# Door_Lock_DE_12.net
KiCad netlist of a schematic drawn in EAGLE
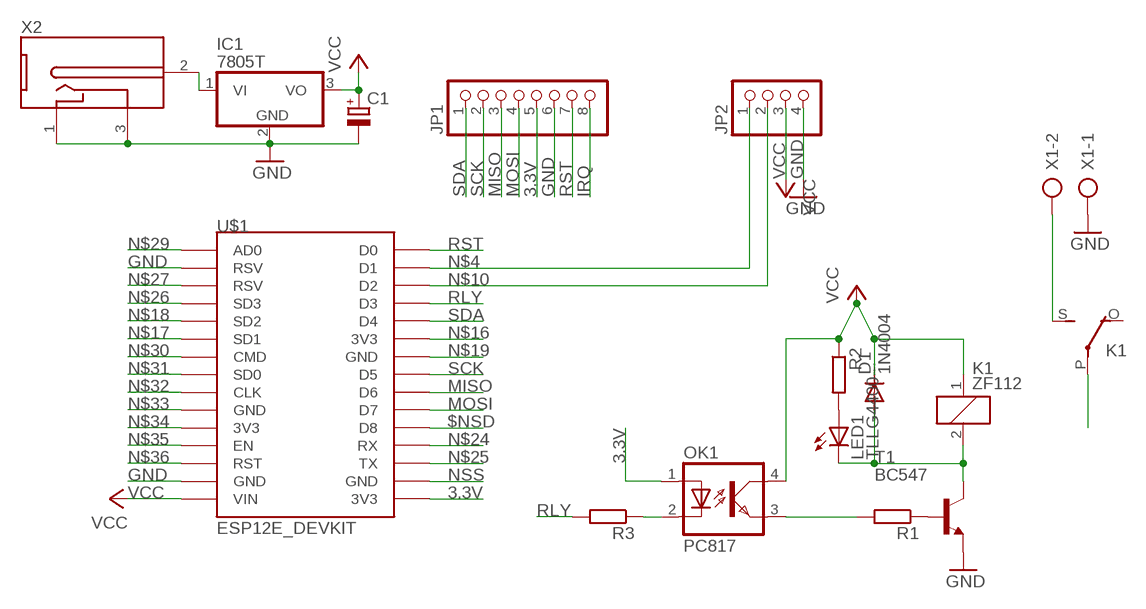
[diagram p0: schematic, sheet 1]

(export (version "E")
  (design (tool "Eeschema 10.0.6"))
  (components
    (comp (ref "C1")
      (value "CPOL-EUE3.5-8")
      (footprint "eagle-import:E3,5-8")
      (libsource (lib "eagle-import") (part "CPOL-EUE3.5-8"))
    )
    (comp (ref "D1")
      (value "1N4004")
      (footprint "eagle-import:DO41-10")
      (libsource (lib "eagle-import") (part "1N4004"))
    )
    (comp (ref "IC1")
      (value "7805T")
      (footprint "eagle-import:TO220H")
      (libsource (lib "eagle-import") (part "78T05"))
    )
    (comp (ref "JP1")
      (value "PINHD-1X8")
      (footprint "eagle-import:1X08")
      (libsource (lib "eagle-import") (part "PINHD-1X8"))
    )
    (comp (ref "JP2")
      (value "PINHD-1X4")
      (footprint "eagle-import:1X04")
      (libsource (lib "eagle-import") (part "PINHD-1X4"))
    )
    (comp (ref "K1")
      (value "ZF112")
      (footprint "eagle-import:ZF112")
      (libsource (lib "eagle-import") (part "ZF112"))
    )
    (comp (ref "LED1")
      (value "TLLG4400")
      (footprint "eagle-import:LED3MM")
      (fields (field (name "MF") "VISHAY SEMICONDUCTOR"))
      (libsource (lib "eagle-import") (part "TLLG4400"))
    )
    (comp (ref "OK1")
      (value "PC817")
      (footprint "eagle-import:DIL04")
      (fields (field (name "MPN") "PC817X4J000F"))
      (libsource (lib "eagle-import") (part "PC817"))
    )
    (comp (ref "R1")
      (value "R-EU_0204/7")
      (footprint "eagle-import:0204_7")
      (libsource (lib "eagle-import") (part "R-EU_0204/7"))
    )
    (comp (ref "R2")
      (value "R-EU_0204/7")
      (footprint "eagle-import:0204_7")
      (libsource (lib "eagle-import") (part "R-EU_0204/7"))
    )
    (comp (ref "R3")
      (value "R-EU_0204/7")
      (footprint "eagle-import:0204_7")
      (libsource (lib "eagle-import") (part "R-EU_0204/7"))
    )
    (comp (ref "T1")
      (value "BC547")
      (footprint "eagle-import:TO92")
      (libsource (lib "eagle-import") (part "BC547"))
    )
    (comp (ref "U$1")
      (value "ESP12E_DEVKIT")
      (footprint "eagle-import:ESP12E_DEVKIT")
      (libsource (lib "eagle-import") (part "ESP12E_DEVKIT"))
    )
    (comp (ref "X1")
      (value "AK300/2")
      (footprint "eagle-import:AK300_2")
      (libsource (lib "eagle-import") (part "AK300/2"))
    )
    (comp (ref "X2")
      (value "DC-2.1MM-5MM")
      (footprint "eagle-import:DC-21MM")
      (libsource (lib "eagle-import") (part "DC-5MM-2.1MM"))
    )
  )
  (nets
    (net (code "1") (name "/$NSD") (class "Default")
      (node (ref "U$1") (pin "D8") (pinfunction "D8_D8") (pintype "bidirectional"))
    )
    (net (code "2") (name "/3.3V") (class "Default")
      (node (ref "JP1") (pin "5") (pinfunction "5_5") (pintype "passive"))
      (node (ref "OK1") (pin "1") (pinfunction "A_1") (pintype "passive"))
      (node (ref "U$1") (pin "3V3@2") (pinfunction "3V3_3V3@2") (pintype "bidirectional"))
    )
    (net (code "3") (name "/IRQ") (class "Default")
      (node (ref "JP1") (pin "8") (pinfunction "8_8") (pintype "passive"))
    )
    (net (code "4") (name "/MISO") (class "Default")
      (node (ref "JP1") (pin "3") (pinfunction "3_3") (pintype "passive"))
      (node (ref "U$1") (pin "D6") (pinfunction "D6_D6") (pintype "bidirectional"))
    )
    (net (code "5") (name "/MOSI") (class "Default")
      (node (ref "JP1") (pin "4") (pinfunction "4_4") (pintype "passive"))
      (node (ref "U$1") (pin "D7") (pinfunction "D7_D7") (pintype "bidirectional"))
    )
    (net (code "6") (name "/N$4") (class "Default")
      (node (ref "JP2") (pin "1") (pinfunction "1_1") (pintype "passive"))
      (node (ref "U$1") (pin "D1") (pinfunction "D1_D1") (pintype "bidirectional"))
    )
    (net (code "7") (name "/N$10") (class "Default")
      (node (ref "JP2") (pin "2") (pinfunction "2_2") (pintype "passive"))
      (node (ref "U$1") (pin "D2") (pinfunction "D2_D2") (pintype "bidirectional"))
    )
    (net (code "8") (name "/N$16") (class "Default")
      (node (ref "U$1") (pin "3V3@1") (pinfunction "3V3_3V3@1") (pintype "bidirectional"))
    )
    (net (code "9") (name "/N$17") (class "Default")
      (node (ref "U$1") (pin "SD1") (pinfunction "SD1_SD1") (pintype "bidirectional"))
    )
    (net (code "10") (name "/N$18") (class "Default")
      (node (ref "U$1") (pin "SD2") (pinfunction "SD2_SD2") (pintype "bidirectional"))
    )
    (net (code "11") (name "/N$19") (class "Default")
      (node (ref "U$1") (pin "GND@2") (pinfunction "GND_GND@2") (pintype "bidirectional"))
    )
    (net (code "12") (name "/N$24") (class "Default")
      (node (ref "U$1") (pin "RX") (pinfunction "RX_RX") (pintype "bidirectional"))
    )
    (net (code "13") (name "/N$25") (class "Default")
      (node (ref "U$1") (pin "TX") (pinfunction "TX_TX") (pintype "bidirectional"))
    )
    (net (code "14") (name "/N$26") (class "Default")
      (node (ref "U$1") (pin "SD3") (pinfunction "SD3_SD3") (pintype "bidirectional"))
    )
    (net (code "15") (name "/N$27") (class "Default")
      (node (ref "U$1") (pin "RSV@1") (pinfunction "RSV_RSV@1") (pintype "bidirectional"))
    )
    (net (code "16") (name "/N$29") (class "Default")
      (node (ref "U$1") (pin "AD0") (pinfunction "AD0_AD0") (pintype "bidirectional"))
    )
    (net (code "17") (name "/N$30") (class "Default")
      (node (ref "U$1") (pin "CMD") (pinfunction "CMD_CMD") (pintype "bidirectional"))
    )
    (net (code "18") (name "/N$31") (class "Default")
      (node (ref "U$1") (pin "SD0") (pinfunction "SD0_SD0") (pintype "bidirectional"))
    )
    (net (code "19") (name "/N$32") (class "Default")
      (node (ref "U$1") (pin "CLK") (pinfunction "CLK_CLK") (pintype "bidirectional"))
    )
    (net (code "20") (name "/N$33") (class "Default")
      (node (ref "U$1") (pin "GND@0") (pinfunction "GND_GND@0") (pintype "bidirectional"))
    )
    (net (code "21") (name "/N$34") (class "Default")
      (node (ref "U$1") (pin "3V3@0") (pinfunction "3V3_3V3@0") (pintype "bidirectional"))
    )
    (net (code "22") (name "/N$35") (class "Default")
      (node (ref "U$1") (pin "EN") (pinfunction "EN_EN") (pintype "bidirectional"))
    )
    (net (code "23") (name "/N$36") (class "Default")
      (node (ref "U$1") (pin "RST") (pinfunction "RST_RST") (pintype "bidirectional"))
    )
    (net (code "24") (name "/NSS") (class "Default")
      (node (ref "U$1") (pin "GND@3") (pinfunction "GND_GND@3") (pintype "bidirectional"))
    )
    (net (code "25") (name "/RLY") (class "Default")
      (node (ref "R3") (pin "2") (pinfunction "2_2") (pintype "passive"))
      (node (ref "U$1") (pin "D3") (pinfunction "D3_D3") (pintype "bidirectional"))
    )
    (net (code "26") (name "/RST") (class "Default")
      (node (ref "JP1") (pin "7") (pinfunction "7_7") (pintype "passive"))
      (node (ref "U$1") (pin "D0") (pinfunction "D0_D0") (pintype "bidirectional"))
    )
    (net (code "27") (name "/SCK") (class "Default")
      (node (ref "JP1") (pin "2") (pinfunction "2_2") (pintype "passive"))
      (node (ref "U$1") (pin "D5") (pinfunction "D5_D5") (pintype "bidirectional"))
    )
    (net (code "28") (name "/SDA") (class "Default")
      (node (ref "JP1") (pin "1") (pinfunction "1_1") (pintype "passive"))
      (node (ref "U$1") (pin "D4") (pinfunction "D4_D4") (pintype "bidirectional"))
    )
    (net (code "29") (name "GND") (class "Default")
      (node (ref "C1") (pin "-") (pinfunction "-_-") (pintype "passive"))
      (node (ref "IC1") (pin "2") (pinfunction "GND_2") (pintype "passive"))
      (node (ref "JP1") (pin "6") (pinfunction "6_6") (pintype "passive"))
      (node (ref "JP2") (pin "4") (pinfunction "4_4") (pintype "passive"))
      (node (ref "T1") (pin "1") (pinfunction "E_1") (pintype "passive"))
      (node (ref "U$1") (pin "GND@1") (pinfunction "GND_GND@1") (pintype "bidirectional"))
      (node (ref "U$1") (pin "RSV@0") (pinfunction "RSV_RSV@0") (pintype "bidirectional"))
      (node (ref "X1") (pin "1") (pinfunction "KL_1") (pintype "passive"))
      (node (ref "X2") (pin "1") (pinfunction "1_1") (pintype "power_in"))
      (node (ref "X2") (pin "3") (pinfunction "2_3") (pintype "power_in"))
    )
    (net (code "30") (name "Net-(IC1-VI)") (class "Default")
      (node (ref "IC1") (pin "1") (pinfunction "VI_1") (pintype "input"))
      (node (ref "X2") (pin "2") (pinfunction "3_2") (pintype "power_in"))
    )
    (net (code "31") (name "Net-(LED1-C)") (class "Default")
      (node (ref "D1") (pin "A") (pinfunction "A_A") (pintype "passive"))
      (node (ref "K1") (pin "2") (pinfunction "2_2") (pintype "passive"))
      (node (ref "LED1") (pin "K") (pinfunction "C_K") (pintype "passive"))
      (node (ref "T1") (pin "3") (pinfunction "C_3") (pintype "passive"))
    )
    (net (code "32") (name "Net-(LED1-PadA)") (class "Default")
      (node (ref "LED1") (pin "A") (pinfunction "A_A") (pintype "passive"))
      (node (ref "R2") (pin "2") (pinfunction "2_2") (pintype "passive"))
    )
    (net (code "33") (name "Net-(OK1-C)") (class "Default")
      (node (ref "OK1") (pin "2") (pinfunction "C_2") (pintype "passive"))
      (node (ref "R3") (pin "1") (pinfunction "1_1") (pintype "passive"))
    )
    (net (code "34") (name "Net-(OK1-EMIT)") (class "Default")
      (node (ref "OK1") (pin "3") (pinfunction "EMIT_3") (pintype "passive"))
      (node (ref "R1") (pin "2") (pinfunction "2_2") (pintype "passive"))
    )
    (net (code "35") (name "Net-(T1-B)") (class "Default")
      (node (ref "R1") (pin "1") (pinfunction "1_1") (pintype "passive"))
      (node (ref "T1") (pin "2") (pinfunction "B_2") (pintype "passive"))
    )
    (net (code "36") (name "Net-(X1B-KL)") (class "Default")
      (node (ref "K1") (pin "S") (pinfunction "S_S") (pintype "passive"))
      (node (ref "X1") (pin "2") (pinfunction "KL_2") (pintype "passive"))
    )
    (net (code "37") (name "VCC") (class "Default")
      (node (ref "C1") (pin "+") (pinfunction "+_+") (pintype "passive"))
      (node (ref "D1") (pin "C") (pinfunction "C_C") (pintype "passive"))
      (node (ref "IC1") (pin "3") (pinfunction "VO_3") (pintype "passive"))
      (node (ref "JP2") (pin "3") (pinfunction "3_3") (pintype "passive"))
      (node (ref "K1") (pin "1") (pinfunction "1_1") (pintype "passive"))
      (node (ref "K1") (pin "P") (pinfunction "P_P") (pintype "passive"))
      (node (ref "OK1") (pin "4") (pinfunction "COL_4") (pintype "passive"))
      (node (ref "R2") (pin "1") (pinfunction "1_1") (pintype "passive"))
      (node (ref "U$1") (pin "VIN") (pinfunction "VIN_VIN") (pintype "bidirectional"))
    )
    (net (code "38") (name "unconnected-(K1-PadO)") (class "Default")
      (node (ref "K1") (pin "O") (pinfunction "O_O") (pintype "passive"))
    )
  )
)
